# Horizontally_Mounted_Lighthouse.net
KiCad netlist of a schematic drawn in EAGLE
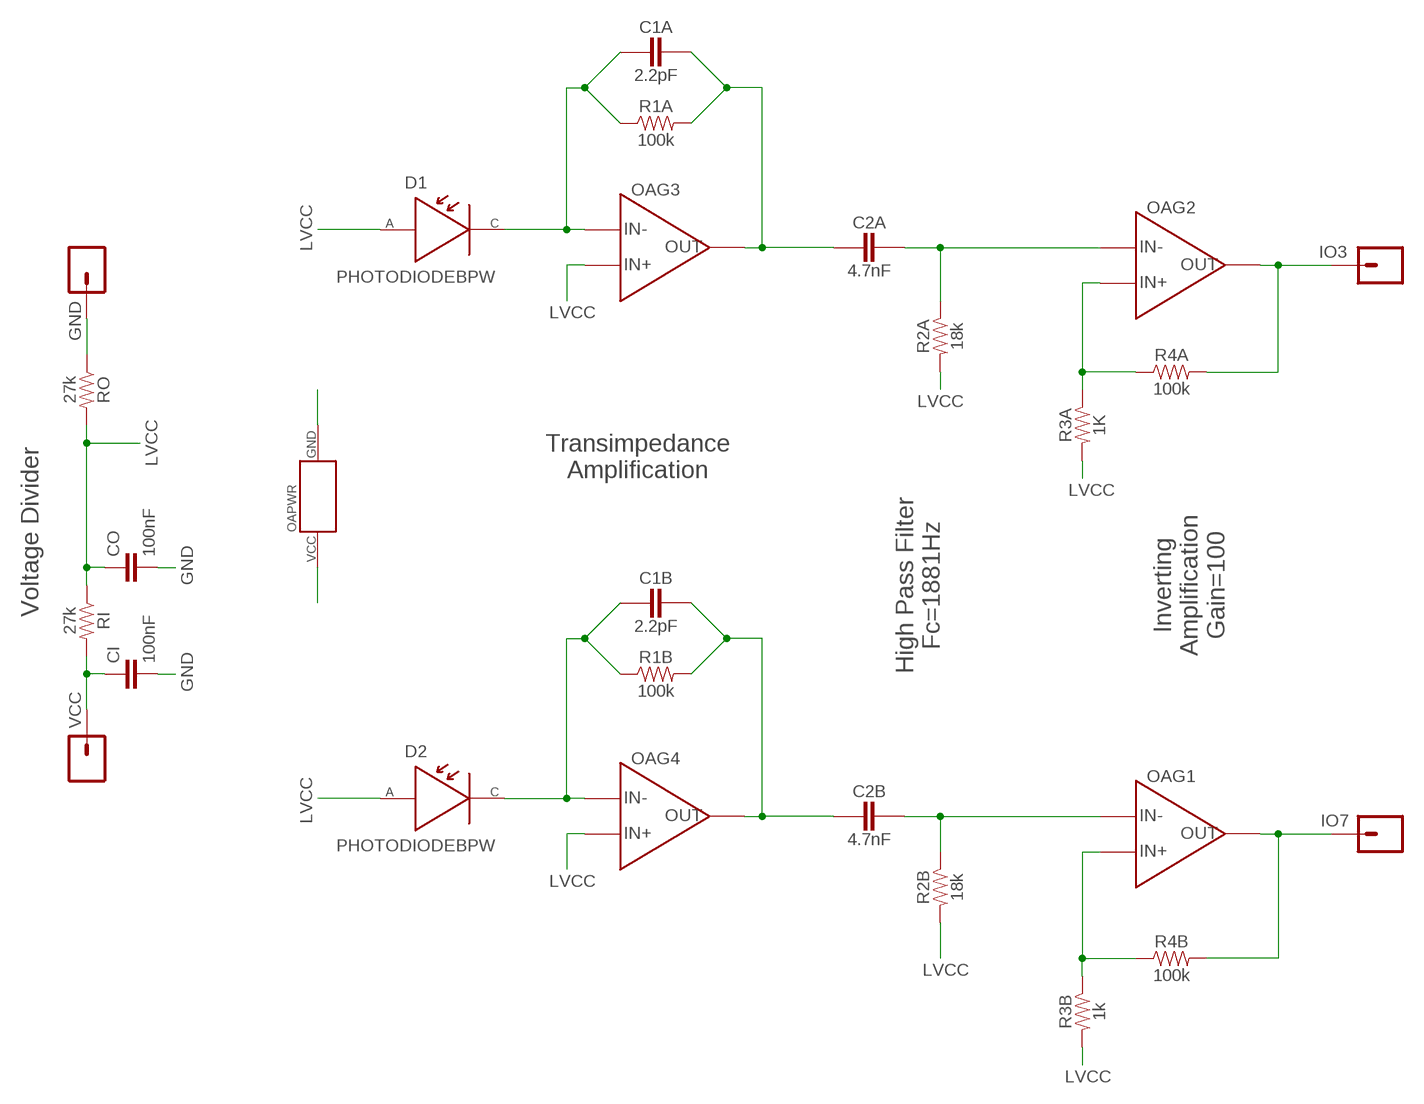
[diagram p0: schematic, sheet 1]

(export (version "E")
  (design (tool "Eeschema 10.0.6"))
  (components
    (comp (ref "C1A")
      (value "2.2pF")
      (footprint "eagle-import:PASSIVE-0603")
      (libsource (lib "eagle-import") (part "CAPACITOR"))
    )
    (comp (ref "C1B")
      (value "2.2pF")
      (footprint "eagle-import:PASSIVE-0603")
      (libsource (lib "eagle-import") (part "CAPACITOR"))
    )
    (comp (ref "C2A")
      (value "4.7nF")
      (footprint "eagle-import:PASSIVE-0603")
      (libsource (lib "eagle-import") (part "CAPACITOR"))
    )
    (comp (ref "C2B")
      (value "4.7nF")
      (footprint "eagle-import:PASSIVE-0603")
      (libsource (lib "eagle-import") (part "CAPACITOR"))
    )
    (comp (ref "CI")
      (value "100nF")
      (footprint "eagle-import:0603")
      (libsource (lib "eagle-import") (part "4.7PF-0603-50V-5%"))
    )
    (comp (ref "CO")
      (value "100nF")
      (footprint "eagle-import:0603")
      (libsource (lib "eagle-import") (part "4.7PF-0603-50V-5%"))
    )
    (comp (ref "D1")
      (value "PHOTODIODEBPW")
      (footprint "eagle-import:BPW34_BP104_SMD")
      (libsource (lib "eagle-import") (part "PHOTODIODEBPW"))
    )
    (comp (ref "D2")
      (value "PHOTODIODEBPW")
      (footprint "eagle-import:BPW34_BP104_SMD")
      (libsource (lib "eagle-import") (part "PHOTODIODEBPW"))
    )
    (comp (ref "GND")
      (value "CONN_01PTH_NO_SILK_YES_STOP")
      (footprint "eagle-import:1X01_NO_SILK")
      (libsource (lib "eagle-import") (part "CONN_01PTH_NO_SILK_YES_STOP"))
    )
    (comp (ref "IO3")
      (value "CONN_01PTH_NO_SILK_YES_STOP")
      (footprint "eagle-import:1X01_NO_SILK")
      (libsource (lib "eagle-import") (part "CONN_01PTH_NO_SILK_YES_STOP"))
    )
    (comp (ref "IO7")
      (value "CONN_01PTH_NO_SILK_YES_STOP")
      (footprint "eagle-import:1X01_NO_SILK")
      (libsource (lib "eagle-import") (part "CONN_01PTH_NO_SILK_YES_STOP"))
    )
    (comp (ref "OA")
      (value "TLV2464IDM")
      (footprint "eagle-import:D14-M")
      (libsource (lib "eagle-import") (part "TLV2464IDM"))
    )
    (comp (ref "R1A")
      (value "100k")
      (footprint "eagle-import:PASSIVE-0603")
      (libsource (lib "eagle-import") (part "RESISTOR"))
    )
    (comp (ref "R1B")
      (value "100k")
      (footprint "eagle-import:PASSIVE-0603")
      (libsource (lib "eagle-import") (part "RESISTOR"))
    )
    (comp (ref "R2A")
      (value "18k")
      (footprint "eagle-import:PASSIVE-0603")
      (libsource (lib "eagle-import") (part "RESISTOR"))
    )
    (comp (ref "R2B")
      (value "18k")
      (footprint "eagle-import:PASSIVE-0603")
      (libsource (lib "eagle-import") (part "RESISTOR"))
    )
    (comp (ref "R3A")
      (value "1K")
      (footprint "eagle-import:PASSIVE-0603")
      (libsource (lib "eagle-import") (part "RESISTOR"))
    )
    (comp (ref "R3B")
      (value "1k")
      (footprint "eagle-import:PASSIVE-0603")
      (libsource (lib "eagle-import") (part "RESISTOR"))
    )
    (comp (ref "R4A")
      (value "100k")
      (footprint "eagle-import:PASSIVE-0603")
      (libsource (lib "eagle-import") (part "RESISTOR"))
    )
    (comp (ref "R4B")
      (value "100k")
      (footprint "eagle-import:PASSIVE-0603")
      (libsource (lib "eagle-import") (part "RESISTOR"))
    )
    (comp (ref "RI")
      (value "27k")
      (footprint "eagle-import:0603")
      (libsource (lib "eagle-import") (part "100KOHM-0603-1/10W-1%"))
    )
    (comp (ref "RO")
      (value "27k")
      (footprint "eagle-import:0603")
      (libsource (lib "eagle-import") (part "100KOHM-0603-1/10W-1%"))
    )
    (comp (ref "VCC")
      (value "CONN_01PTH_NO_SILK_YES_STOP")
      (footprint "eagle-import:1X01_NO_SILK")
      (libsource (lib "eagle-import") (part "CONN_01PTH_NO_SILK_YES_STOP"))
    )
  )
  (nets
    (net (code "1") (name "/GND") (class "Default")
      (node (ref "CI") (pin "2") (pinfunction "2_2") (pintype "passive"))
      (node (ref "CO") (pin "2") (pinfunction "2_2") (pintype "passive"))
      (node (ref "GND") (pin "1") (pinfunction "1_1") (pintype "passive"))
      (node (ref "OA") (pin "11") (pinfunction "GND_11") (pintype "bidirectional"))
      (node (ref "RO") (pin "1") (pinfunction "1_1") (pintype "passive"))
    )
    (net (code "2") (name "/IO3") (class "Default")
      (node (ref "IO3") (pin "1") (pinfunction "1_1") (pintype "passive"))
      (node (ref "OA") (pin "7") (pinfunction "OUT_7") (pintype "bidirectional"))
      (node (ref "R4A") (pin "2") (pinfunction "2_2") (pintype "passive"))
    )
    (net (code "3") (name "/IO7") (class "Default")
      (node (ref "IO7") (pin "1") (pinfunction "1_1") (pintype "passive"))
      (node (ref "OA") (pin "1") (pinfunction "OUT_1") (pintype "bidirectional"))
      (node (ref "R4B") (pin "2") (pinfunction "2_2") (pintype "passive"))
    )
    (net (code "4") (name "/LVCC") (class "Default")
      (node (ref "CO") (pin "1") (pinfunction "1_1") (pintype "passive"))
      (node (ref "D1") (pin "ANODE") (pinfunction "ANODE_ANODE") (pintype "bidirectional"))
      (node (ref "D2") (pin "ANODE") (pinfunction "ANODE_ANODE") (pintype "bidirectional"))
      (node (ref "OA") (pin "10") (pinfunction "IN+_10") (pintype "bidirectional"))
      (node (ref "OA") (pin "12") (pinfunction "IN+_12") (pintype "bidirectional"))
      (node (ref "R2A") (pin "2") (pinfunction "2_2") (pintype "passive"))
      (node (ref "R2B") (pin "2") (pinfunction "2_2") (pintype "passive"))
      (node (ref "R3A") (pin "2") (pinfunction "2_2") (pintype "passive"))
      (node (ref "R3B") (pin "2") (pinfunction "2_2") (pintype "passive"))
      (node (ref "RI") (pin "1") (pinfunction "1_1") (pintype "passive"))
      (node (ref "RO") (pin "2") (pinfunction "2_2") (pintype "passive"))
    )
    (net (code "5") (name "/VCC") (class "Default")
      (node (ref "CI") (pin "1") (pinfunction "1_1") (pintype "passive"))
      (node (ref "OA") (pin "4") (pinfunction "VCC_4") (pintype "bidirectional"))
      (node (ref "RI") (pin "2") (pinfunction "2_2") (pintype "passive"))
      (node (ref "VCC") (pin "1") (pinfunction "1_1") (pintype "passive"))
    )
    (net (code "6") (name "Net-(OAA-IN+)") (class "Default")
      (node (ref "OA") (pin "3") (pinfunction "IN+_3") (pintype "bidirectional"))
      (node (ref "R3B") (pin "1") (pinfunction "1_1") (pintype "passive"))
      (node (ref "R4B") (pin "1") (pinfunction "1_1") (pintype "passive"))
    )
    (net (code "7") (name "Net-(OAA-IN-)") (class "Default")
      (node (ref "C2B") (pin "2") (pinfunction "2_2") (pintype "passive"))
      (node (ref "OA") (pin "2") (pinfunction "IN-_2") (pintype "bidirectional"))
      (node (ref "R2B") (pin "1") (pinfunction "1_1") (pintype "passive"))
    )
    (net (code "8") (name "Net-(OAB-IN+)") (class "Default")
      (node (ref "OA") (pin "5") (pinfunction "IN+_5") (pintype "bidirectional"))
      (node (ref "R3A") (pin "1") (pinfunction "1_1") (pintype "passive"))
      (node (ref "R4A") (pin "1") (pinfunction "1_1") (pintype "passive"))
    )
    (net (code "9") (name "Net-(OAB-IN-)") (class "Default")
      (node (ref "C2A") (pin "2") (pinfunction "2_2") (pintype "passive"))
      (node (ref "OA") (pin "6") (pinfunction "IN-_6") (pintype "bidirectional"))
      (node (ref "R2A") (pin "1") (pinfunction "1_1") (pintype "passive"))
    )
    (net (code "10") (name "Net-(OAC-IN-)") (class "Default")
      (node (ref "C1A") (pin "1") (pinfunction "1_1") (pintype "passive"))
      (node (ref "D1") (pin "CATHODE") (pinfunction "CATHODE_CATHODE") (pintype "bidirectional"))
      (node (ref "OA") (pin "9") (pinfunction "IN-_9") (pintype "bidirectional"))
      (node (ref "R1A") (pin "1") (pinfunction "1_1") (pintype "passive"))
    )
    (net (code "11") (name "Net-(OAC-OUT)") (class "Default")
      (node (ref "C1A") (pin "2") (pinfunction "2_2") (pintype "passive"))
      (node (ref "C2A") (pin "1") (pinfunction "1_1") (pintype "passive"))
      (node (ref "OA") (pin "8") (pinfunction "OUT_8") (pintype "bidirectional"))
      (node (ref "R1A") (pin "2") (pinfunction "2_2") (pintype "passive"))
    )
    (net (code "12") (name "Net-(OAD-IN-)") (class "Default")
      (node (ref "C1B") (pin "1") (pinfunction "1_1") (pintype "passive"))
      (node (ref "D2") (pin "CATHODE") (pinfunction "CATHODE_CATHODE") (pintype "bidirectional"))
      (node (ref "OA") (pin "13") (pinfunction "IN-_13") (pintype "bidirectional"))
      (node (ref "R1B") (pin "1") (pinfunction "1_1") (pintype "passive"))
    )
    (net (code "13") (name "Net-(OAD-OUT)") (class "Default")
      (node (ref "C1B") (pin "2") (pinfunction "2_2") (pintype "passive"))
      (node (ref "C2B") (pin "1") (pinfunction "1_1") (pintype "passive"))
      (node (ref "OA") (pin "14") (pinfunction "OUT_14") (pintype "bidirectional"))
      (node (ref "R1B") (pin "2") (pinfunction "2_2") (pintype "passive"))
    )
  )
)
